# bridge.net
KiCad netlist of a schematic drawn in EAGLE
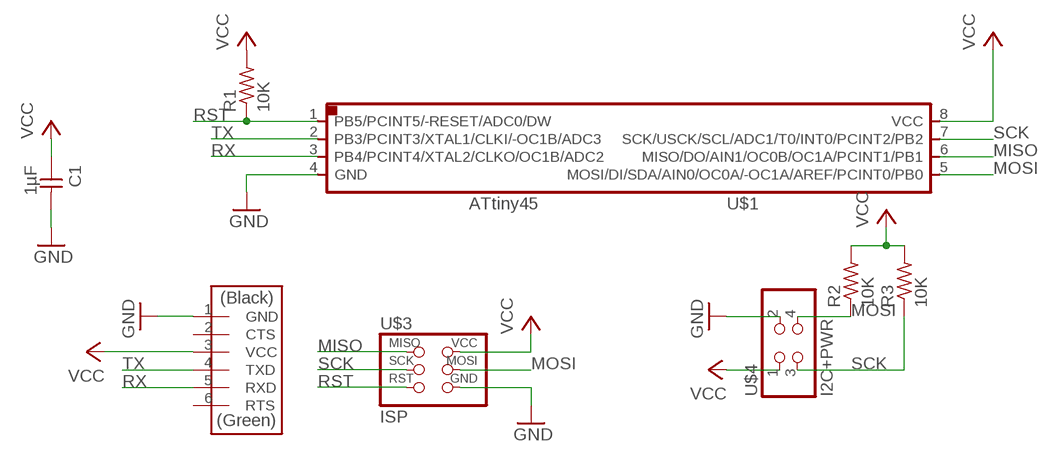
[diagram p0: schematic, sheet 1]

(export (version "E")
  (design (tool "Eeschema 10.0.6"))
  (components
    (comp (ref "C1")
      (value "1µF")
      (footprint "eagle-import:C1206FAB")
      (libsource (lib "eagle-import") (part "CAP-UNPOLARIZEDFAB"))
    )
    (comp (ref "R1")
      (value "10K")
      (footprint "eagle-import:R1206FAB")
      (libsource (lib "eagle-import") (part "RES-US1206FAB"))
    )
    (comp (ref "R2")
      (value "10K")
      (footprint "eagle-import:R1206FAB")
      (libsource (lib "eagle-import") (part "RES-US1206FAB"))
    )
    (comp (ref "R3")
      (value "10K")
      (footprint "eagle-import:R1206FAB")
      (libsource (lib "eagle-import") (part "RES-US1206FAB"))
    )
    (comp (ref "U$1")
      (value "ATTINY45SI")
      (footprint "eagle-import:SOIC8")
      (libsource (lib "eagle-import") (part "ATTINY45SI"))
    )
    (comp (ref "U$2")
      (value "FTDI-SMD-HEADER")
      (footprint "eagle-import:1X06SMD")
      (libsource (lib "eagle-import") (part "FTDI-SMD-HEADER"))
    )
    (comp (ref "U$3")
      (value "ISP")
      (footprint "eagle-import:2X03SMD")
      (libsource (lib "eagle-import") (part "AVRISPSMD"))
    )
    (comp (ref "U$4")
      (value "I2C+PWR")
      (footprint "eagle-import:2X02SMD")
      (libsource (lib "eagle-import") (part "PINHD-2X2-SMD"))
    )
  )
  (nets
    (net (code "1") (name "/MISO") (class "Default")
      (node (ref "U$1") (pin "6") (pinfunction "MISO/DO/AIN1/OC0B/OC1A/PCINT1/PB1_6") (pintype "bidirectional"))
      (node (ref "U$3") (pin "1") (pinfunction "MISO_1") (pintype "passive"))
    )
    (net (code "2") (name "/MOSI") (class "Default")
      (node (ref "R2") (pin "1") (pinfunction "1_1") (pintype "passive"))
      (node (ref "U$1") (pin "5") (pinfunction "MOSI/DI/SDA/AIN0/OC0A/-OC1A/AREF/PCINT0/PB0_5") (pintype "bidirectional"))
      (node (ref "U$3") (pin "4") (pinfunction "MOSI_4") (pintype "passive"))
      (node (ref "U$4") (pin "4") (pinfunction "4_4") (pintype "passive"))
    )
    (net (code "3") (name "/RST") (class "Default")
      (node (ref "R1") (pin "1") (pinfunction "1_1") (pintype "passive"))
      (node (ref "U$1") (pin "1") (pinfunction "PB5/PCINT5/-RESET/ADC0/DW_1") (pintype "bidirectional"))
      (node (ref "U$3") (pin "5") (pinfunction "RST_5") (pintype "passive"))
    )
    (net (code "4") (name "/RX") (class "Default")
      (node (ref "U$1") (pin "3") (pinfunction "PB4/PCINT4/XTAL2/CLKO/OC1B/ADC2_3") (pintype "bidirectional"))
      (node (ref "U$2") (pin "5") (pinfunction "RXD_5") (pintype "bidirectional"))
    )
    (net (code "5") (name "/SCK") (class "Default")
      (node (ref "R3") (pin "1") (pinfunction "1_1") (pintype "passive"))
      (node (ref "U$1") (pin "7") (pinfunction "SCK/USCK/SCL/ADC1/T0/INT0/PCINT2/PB2_7") (pintype "bidirectional"))
      (node (ref "U$3") (pin "3") (pinfunction "SCK_3") (pintype "passive"))
      (node (ref "U$4") (pin "3") (pinfunction "3_3") (pintype "passive"))
    )
    (net (code "6") (name "/TX") (class "Default")
      (node (ref "U$1") (pin "2") (pinfunction "PB3/PCINT3/XTAL1/CLKI/-OC1B/ADC3_2") (pintype "bidirectional"))
      (node (ref "U$2") (pin "4") (pinfunction "TXD_4") (pintype "bidirectional"))
    )
    (net (code "7") (name "GND") (class "Default")
      (node (ref "C1") (pin "2") (pinfunction "2_2") (pintype "passive"))
      (node (ref "U$1") (pin "4") (pinfunction "GND_4") (pintype "bidirectional"))
      (node (ref "U$2") (pin "1") (pinfunction "GND_1") (pintype "bidirectional"))
      (node (ref "U$3") (pin "6") (pinfunction "GND_6") (pintype "passive"))
      (node (ref "U$4") (pin "2") (pinfunction "2_2") (pintype "passive"))
    )
    (net (code "8") (name "VCC") (class "Default")
      (node (ref "C1") (pin "1") (pinfunction "1_1") (pintype "passive"))
      (node (ref "R1") (pin "2") (pinfunction "2_2") (pintype "passive"))
      (node (ref "R2") (pin "2") (pinfunction "2_2") (pintype "passive"))
      (node (ref "R3") (pin "2") (pinfunction "2_2") (pintype "passive"))
      (node (ref "U$1") (pin "8") (pinfunction "VCC_8") (pintype "bidirectional"))
      (node (ref "U$2") (pin "3") (pinfunction "VCC_3") (pintype "bidirectional"))
      (node (ref "U$3") (pin "2") (pinfunction "VCC_2") (pintype "passive"))
      (node (ref "U$4") (pin "1") (pinfunction "1_1") (pintype "passive"))
    )
    (net (code "9") (name "unconnected-(U$2-CTS-Pad2)") (class "Default")
      (node (ref "U$2") (pin "2") (pinfunction "CTS_2") (pintype "bidirectional"))
    )
    (net (code "10") (name "unconnected-(U$2-RTS-Pad6)") (class "Default")
      (node (ref "U$2") (pin "6") (pinfunction "RTS_6") (pintype "bidirectional"))
    )
  )
)
